# SCH_ymu762-1_2022-05-05.net
KiCad netlist of a schematic drawn in EasyEDA
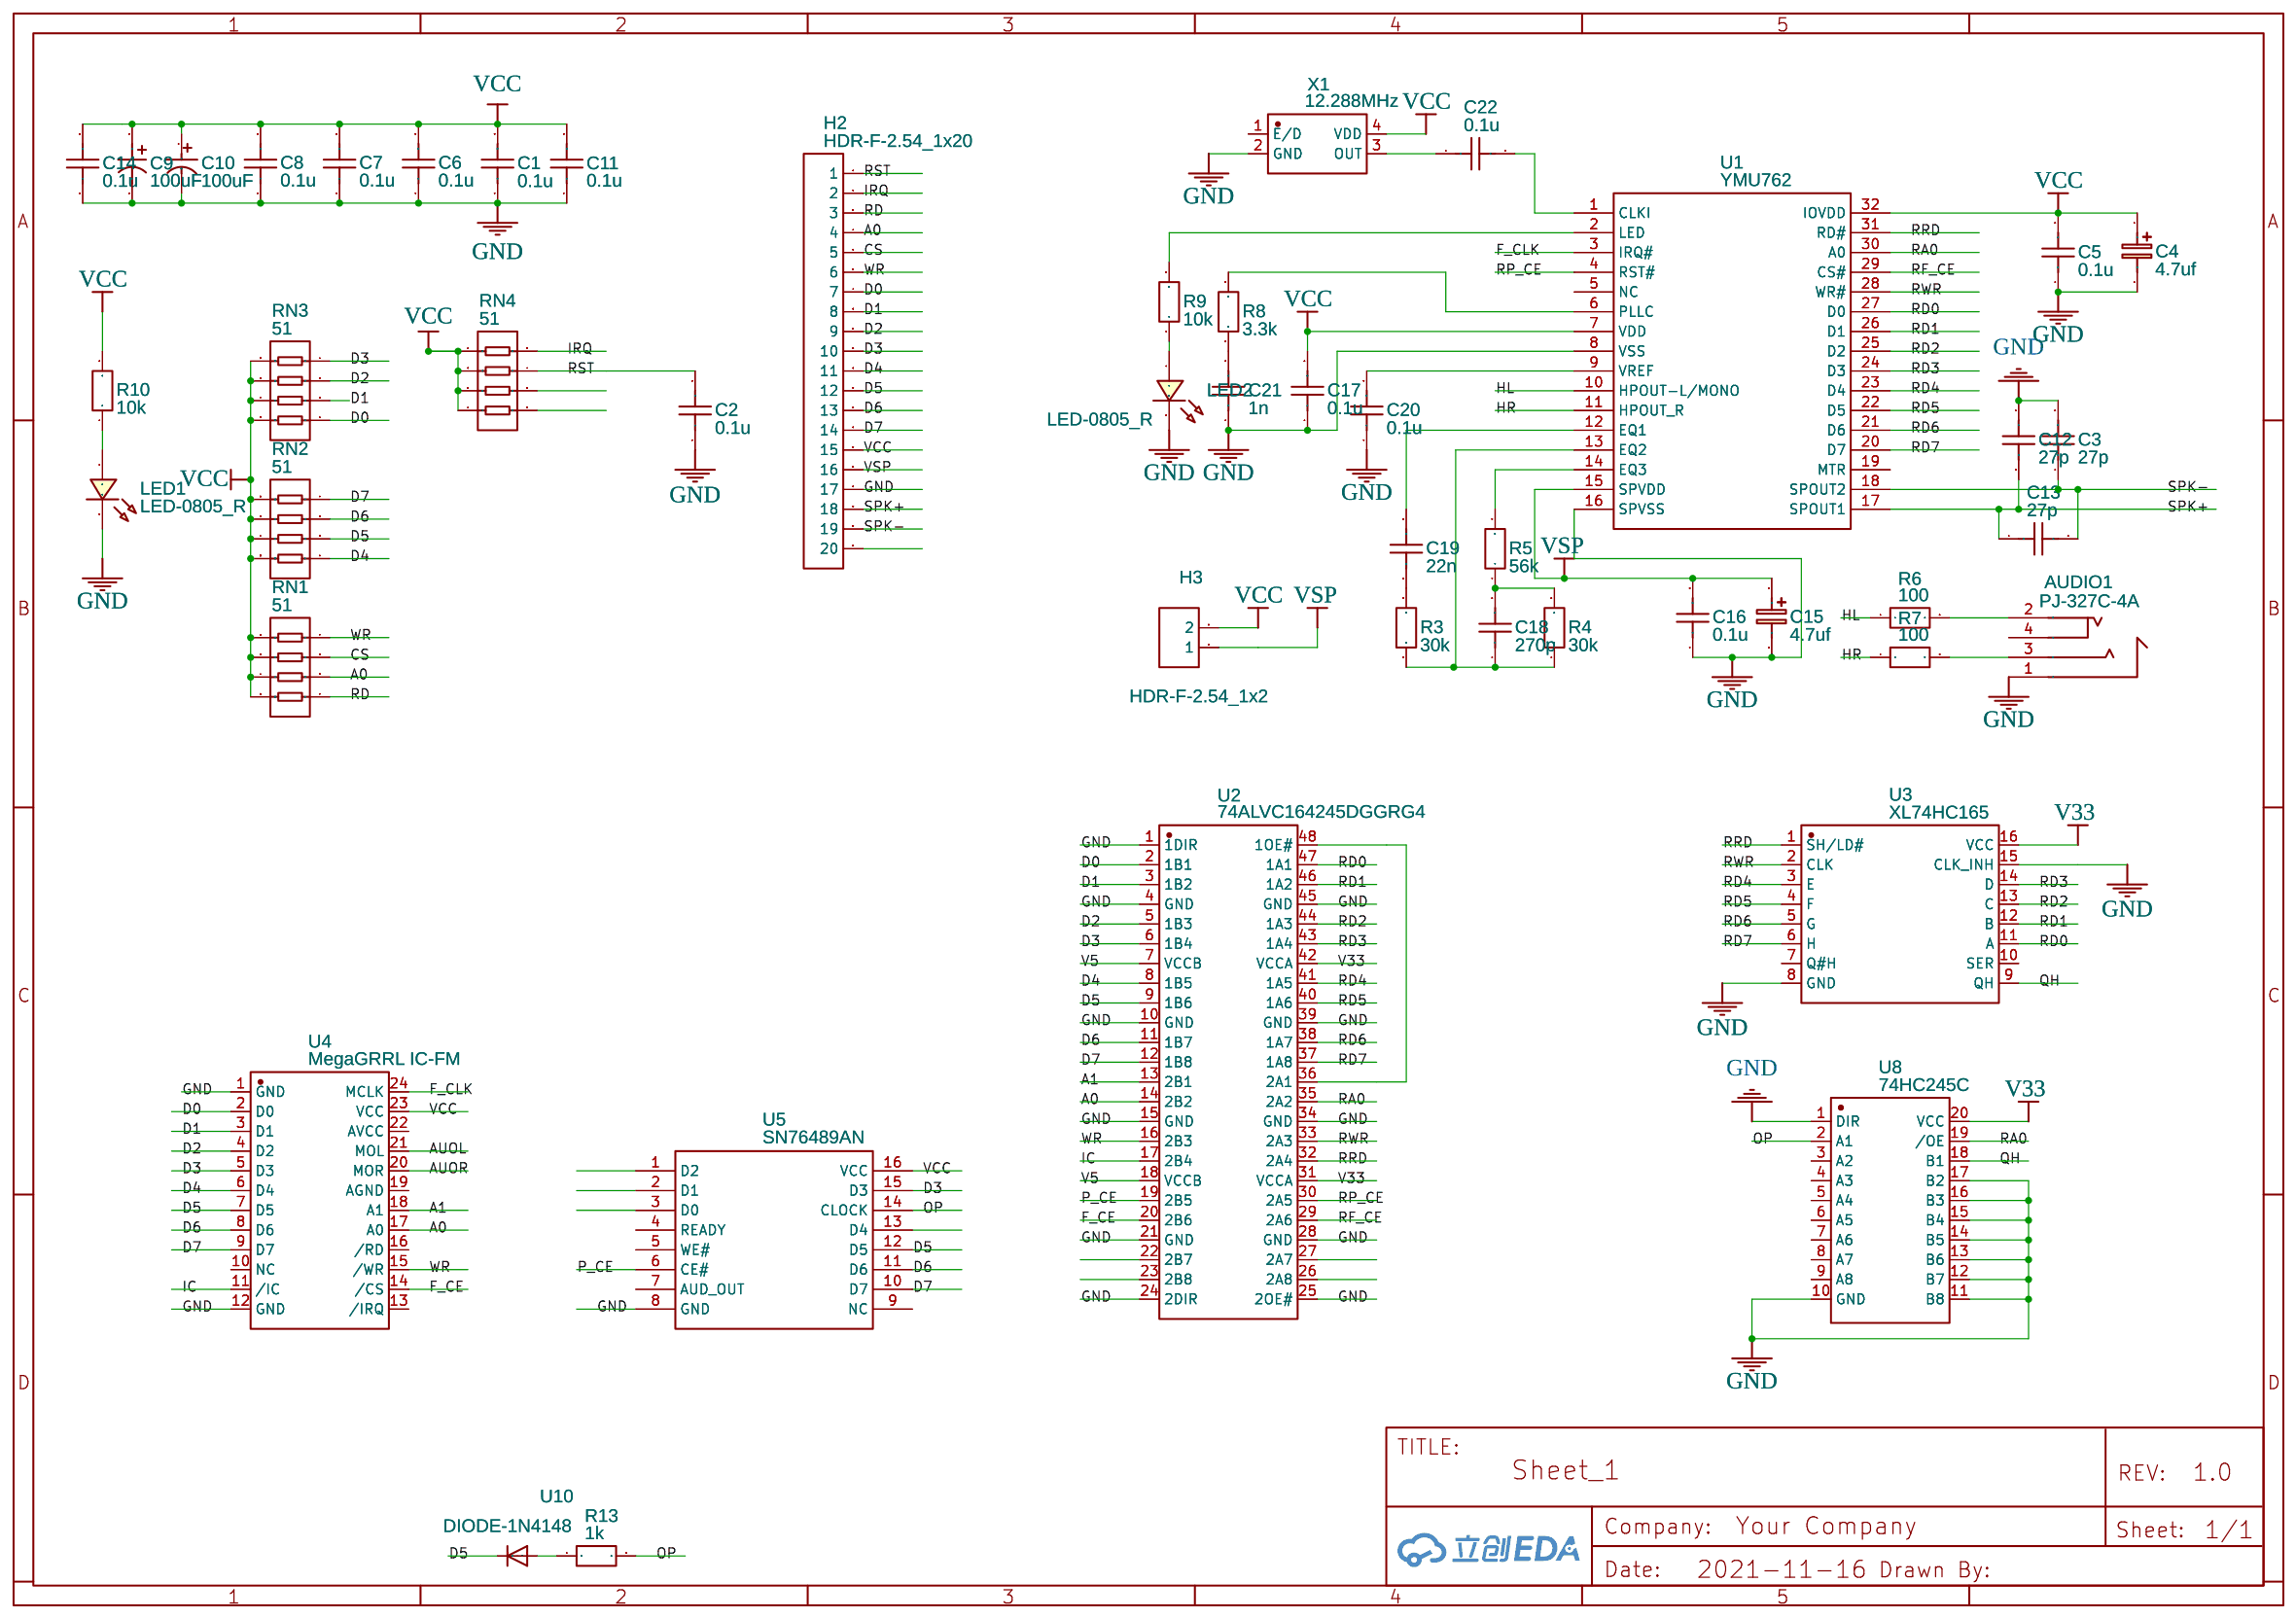
[diagram p0: schematic sheet]

(export (version "E")
  (design (tool "Eeschema 10.0.6"))
  (components
    (comp (ref "AUDIO1")
      (value "PJ-327C-4A")
      (fields (field (name "BOM_Supplier Part") "C145813"))
      (libsource (lib "") (part "PJ-327C-4A"))
    )
    (comp (ref "C1") (value "0.1u") (libsource (lib "") (part "C_0805_US")))
    (comp (ref "C2") (value "0.1u") (libsource (lib "") (part "C_0805_US")))
    (comp (ref "C3") (value "27p") (libsource (lib "") (part "C_0805_US")))
    (comp (ref "C4") (value "4.7uf") (libsource (lib "") (part "C_Tan_SMD_A_EU")))
    (comp (ref "C5") (value "0.1u") (libsource (lib "") (part "C_0805_US")))
    (comp (ref "C6") (value "0.1u") (libsource (lib "") (part "C_0805_US")))
    (comp (ref "C7") (value "0.1u") (libsource (lib "") (part "C_0805_US")))
    (comp (ref "C8") (value "0.1u") (libsource (lib "") (part "C_0805_US")))
    (comp (ref "C9")
      (value "100uF")
      (fields
        (field (name "BOM_Manufacturer Part") "RVT100UF35V67RV0034")
        (field (name "BOM_Supplier Part") "C2836442")
      )
      (libsource (lib "") (part "RVT100UF35V67RV0034"))
    )
    (comp (ref "C10")
      (value "100uF")
      (fields
        (field (name "BOM_Manufacturer Part") "63V 100uF 8X12")
        (field (name "BOM_Supplier Part") "C2772")
      )
      (libsource (lib "") (part "63V 100uF 8X12"))
    )
    (comp (ref "C11") (value "0.1u") (libsource (lib "") (part "C_0805_US")))
    (comp (ref "C12") (value "27p") (libsource (lib "") (part "C_0805_US_2")))
    (comp (ref "C13") (value "27p") (libsource (lib "") (part "C_0805_US_1")))
    (comp (ref "C14") (value "0.1u") (libsource (lib "") (part "C_0805_US")))
    (comp (ref "C15") (value "4.7uf") (libsource (lib "") (part "C_Tan_SMD_A_EU_1")))
    (comp (ref "C16") (value "0.1u") (libsource (lib "") (part "C_0805_US")))
    (comp (ref "C17") (value "0.1u") (libsource (lib "") (part "C_0805_US")))
    (comp (ref "C18") (value "270p") (libsource (lib "") (part "C_0805_US")))
    (comp (ref "C19") (value "22n") (libsource (lib "") (part "C_0805_US_2")))
    (comp (ref "C20") (value "0.1u") (libsource (lib "") (part "C_0805_US")))
    (comp (ref "C21") (value "1n") (libsource (lib "") (part "C_0805_US")))
    (comp (ref "C22") (value "0.1u") (libsource (lib "") (part "C_0805_US_1")))
    (comp (ref "H2")
      (value "HDR-F-2.54_1x20")
      (fields (field (name "BOM_Supplier Part") "C50984"))
      (libsource (lib "") (part "HDR-F-2.54_1x20"))
    )
    (comp (ref "H3")
      (value "HDR-F-2.54_1x2")
      (fields (field (name "BOM_Supplier Part") "C49661"))
      (libsource (lib "") (part "HDR-F-2.54_1x2"))
    )
    (comp (ref "LED1")
      (value "LED-0805_R")
      (fields
        (field (name "BOM_Manufacturer Part") "17-21SURC/S530-A3/TR8")
        (field (name "BOM_Supplier Part") "C72037")
      )
      (libsource (lib "") (part "LED-0805_R"))
    )
    (comp (ref "LED2")
      (value "LED-0805_R")
      (fields
        (field (name "BOM_Manufacturer Part") "17-21SURC/S530-A3/TR8")
        (field (name "BOM_Supplier Part") "C72037")
      )
      (libsource (lib "") (part "LED-0805_R"))
    )
    (comp (ref "R3") (value "30k") (libsource (lib "") (part "R_0805_EU")))
    (comp (ref "R4") (value "30k") (libsource (lib "") (part "R_0805_EU")))
    (comp (ref "R5") (value "56k") (libsource (lib "") (part "R_0805_EU")))
    (comp (ref "R6") (value "100") (libsource (lib "") (part "R_0805_EU_1")))
    (comp (ref "R7") (value "100") (libsource (lib "") (part "R_0805_EU_1")))
    (comp (ref "R8") (value "3.3k") (libsource (lib "") (part "R_0805_EU")))
    (comp (ref "R9") (value "10k") (libsource (lib "") (part "R_0805_EU")))
    (comp (ref "R10") (value "10k") (libsource (lib "") (part "R_0805_EU")))
    (comp (ref "R13") (value "1k") (libsource (lib "") (part "R_0805_EU_1")))
    (comp (ref "RN1")
      (value "51")
      (fields
        (field (name "BOM_Manufacturer Part") "YC164-JR-0751RL")
        (field (name "BOM_Supplier Part") "C13474")
      )
      (libsource (lib "") (part "YC164-JR-0751RL_1"))
    )
    (comp (ref "RN2")
      (value "51")
      (fields
        (field (name "BOM_Manufacturer Part") "YC164-JR-0751RL")
        (field (name "BOM_Supplier Part") "C13474")
      )
      (libsource (lib "") (part "YC164-JR-0751RL_1"))
    )
    (comp (ref "RN3")
      (value "51")
      (fields
        (field (name "BOM_Manufacturer Part") "YC164-JR-0751RL")
        (field (name "BOM_Supplier Part") "C13474")
      )
      (libsource (lib "") (part "YC164-JR-0751RL_1"))
    )
    (comp (ref "RN4")
      (value "51")
      (fields
        (field (name "BOM_Manufacturer Part") "YC164-JR-0751RL")
        (field (name "BOM_Supplier Part") "C13474")
      )
      (libsource (lib "") (part "YC164-JR-0751RL"))
    )
    (comp (ref "U1") (value "YMU762") (libsource (lib "") (part "YMU762")))
    (comp (ref "U2")
      (value "74ALVC164245DGGRG4")
      (fields (field (name "BOM_Supplier Part") "C2677427"))
      (libsource (lib "") (part "74ALVC164245DGGRG4"))
    )
    (comp (ref "U3")
      (value "XL74HC165")
      (fields (field (name "BOM_Supplier Part") "C609780"))
      (libsource (lib "") (part "XL74HC165"))
    )
    (comp (ref "U4")
      (value "MegaGRRL IC-FM")
      (fields (field (name "BOM_Manufacturer Part") "YM2612") (field (name "BOM_Supplier Part") "C707077"))
      (libsource (lib "") (part "MegaGRRL IC-FM"))
    )
    (comp (ref "U5") (value "SN76489AN") (libsource (lib "") (part "SN76489AN")))
    (comp (ref "U8")
      (value "74HC245C")
      (fields (field (name "BOM_Supplier Part") "C126198"))
      (libsource (lib "") (part "74HC245C"))
    )
    (comp (ref "U10") (value "DIODE-1N4148") (libsource (lib "") (part "DIODE-1N4148")))
    (comp (ref "X1")
      (value "12.288MHz")
      (fields
        (field (name "BOM_Manufacturer Part") "OT705012.288MJBA4SL")
        (field (name "BOM_Supplier Part") "C669092")
      )
      (libsource (lib "") (part "OT705012.288MJBA4SL"))
    )
  )
  (nets
    (net (code "1") (name "/A0") (class "Default")
      (node (ref "H2") (pin "4") (pinfunction "4_4") (pintype "unspecified"))
      (node (ref "RN1") (pin "2") (pinfunction "2_2") (pintype "unspecified"))
      (node (ref "U2") (pin "14") (pinfunction "2B2_14") (pintype "unspecified"))
      (node (ref "U4") (pin "17") (pinfunction "A0_17") (pintype "unspecified"))
    )
    (net (code "2") (name "/A1") (class "Default")
      (node (ref "U2") (pin "13") (pinfunction "2B1_13") (pintype "unspecified"))
      (node (ref "U4") (pin "18") (pinfunction "A1_18") (pintype "unspecified"))
    )
    (net (code "3") (name "/AUOL") (class "Default")
      (node (ref "U4") (pin "21") (pinfunction "MOL_21") (pintype "unspecified"))
    )
    (net (code "4") (name "/AUOR") (class "Default")
      (node (ref "U4") (pin "20") (pinfunction "MOR_20") (pintype "unspecified"))
    )
    (net (code "5") (name "/CS") (class "Default")
      (node (ref "H2") (pin "5") (pinfunction "5_5") (pintype "unspecified"))
      (node (ref "RN1") (pin "3") (pinfunction "3_3") (pintype "unspecified"))
    )
    (net (code "6") (name "/D0") (class "Default")
      (node (ref "H2") (pin "7") (pinfunction "7_7") (pintype "unspecified"))
      (node (ref "RN3") (pin "1") (pinfunction "1_1") (pintype "unspecified"))
      (node (ref "U2") (pin "2") (pinfunction "1B1_2") (pintype "unspecified"))
      (node (ref "U4") (pin "2") (pinfunction "D0_2") (pintype "unspecified"))
    )
    (net (code "7") (name "/D1") (class "Default")
      (node (ref "H2") (pin "8") (pinfunction "8_8") (pintype "unspecified"))
      (node (ref "RN3") (pin "2") (pinfunction "2_2") (pintype "unspecified"))
      (node (ref "U2") (pin "3") (pinfunction "1B2_3") (pintype "unspecified"))
      (node (ref "U4") (pin "3") (pinfunction "D1_3") (pintype "unspecified"))
    )
    (net (code "8") (name "/D2") (class "Default")
      (node (ref "H2") (pin "9") (pinfunction "9_9") (pintype "unspecified"))
      (node (ref "RN3") (pin "3") (pinfunction "3_3") (pintype "unspecified"))
      (node (ref "U2") (pin "5") (pinfunction "1B3_5") (pintype "unspecified"))
      (node (ref "U4") (pin "4") (pinfunction "D2_4") (pintype "unspecified"))
    )
    (net (code "9") (name "/D3") (class "Default")
      (node (ref "H2") (pin "10") (pinfunction "10_10") (pintype "unspecified"))
      (node (ref "RN3") (pin "4") (pinfunction "4_4") (pintype "unspecified"))
      (node (ref "U2") (pin "6") (pinfunction "1B4_6") (pintype "unspecified"))
      (node (ref "U4") (pin "5") (pinfunction "D3_5") (pintype "unspecified"))
      (node (ref "U5") (pin "15") (pinfunction "D3_15") (pintype "unspecified"))
    )
    (net (code "10") (name "/D4") (class "Default")
      (node (ref "H2") (pin "11") (pinfunction "11_11") (pintype "unspecified"))
      (node (ref "RN2") (pin "1") (pinfunction "1_1") (pintype "unspecified"))
      (node (ref "U2") (pin "8") (pinfunction "1B5_8") (pintype "unspecified"))
      (node (ref "U4") (pin "6") (pinfunction "D4_6") (pintype "unspecified"))
    )
    (net (code "11") (name "/D5") (class "Default")
      (node (ref "H2") (pin "12") (pinfunction "12_12") (pintype "unspecified"))
      (node (ref "RN2") (pin "2") (pinfunction "2_2") (pintype "unspecified"))
      (node (ref "U10") (pin "1") (pinfunction "C_1") (pintype "unspecified"))
      (node (ref "U2") (pin "9") (pinfunction "1B6_9") (pintype "unspecified"))
      (node (ref "U4") (pin "7") (pinfunction "D5_7") (pintype "unspecified"))
      (node (ref "U5") (pin "12") (pinfunction "D5_12") (pintype "unspecified"))
    )
    (net (code "12") (name "/D6") (class "Default")
      (node (ref "H2") (pin "13") (pinfunction "13_13") (pintype "unspecified"))
      (node (ref "RN2") (pin "3") (pinfunction "3_3") (pintype "unspecified"))
      (node (ref "U2") (pin "11") (pinfunction "1B7_11") (pintype "unspecified"))
      (node (ref "U4") (pin "8") (pinfunction "D6_8") (pintype "unspecified"))
      (node (ref "U5") (pin "11") (pinfunction "D6_11") (pintype "unspecified"))
    )
    (net (code "13") (name "/D7") (class "Default")
      (node (ref "H2") (pin "14") (pinfunction "14_14") (pintype "unspecified"))
      (node (ref "RN2") (pin "4") (pinfunction "4_4") (pintype "unspecified"))
      (node (ref "U2") (pin "12") (pinfunction "1B8_12") (pintype "unspecified"))
      (node (ref "U4") (pin "9") (pinfunction "D7_9") (pintype "unspecified"))
      (node (ref "U5") (pin "10") (pinfunction "D7_10") (pintype "unspecified"))
    )
    (net (code "14") (name "/F_CE") (class "Default")
      (node (ref "U2") (pin "20") (pinfunction "2B6_20") (pintype "unspecified"))
      (node (ref "U4") (pin "14") (pinfunction "/CS_14") (pintype "unspecified"))
    )
    (net (code "15") (name "/F_CLK") (class "Default")
      (node (ref "U1") (pin "3") (pinfunction "IRQ#_3") (pintype "unspecified"))
      (node (ref "U4") (pin "24") (pinfunction "MCLK_24") (pintype "unspecified"))
    )
    (net (code "16") (name "/HL") (class "Default")
      (node (ref "R6") (pin "1") (pinfunction "1_1") (pintype "unspecified"))
      (node (ref "U1") (pin "10") (pinfunction "HPOUT-L/MONO_10") (pintype "unspecified"))
    )
    (net (code "17") (name "/HR") (class "Default")
      (node (ref "R7") (pin "1") (pinfunction "1_1") (pintype "unspecified"))
      (node (ref "U1") (pin "11") (pinfunction "HPOUT_R_11") (pintype "unspecified"))
    )
    (net (code "18") (name "/IC") (class "Default")
      (node (ref "U2") (pin "17") (pinfunction "2B4_17") (pintype "unspecified"))
      (node (ref "U4") (pin "11") (pinfunction "/IC_11") (pintype "unspecified"))
    )
    (net (code "19") (name "/IRQ") (class "Default")
      (node (ref "H2") (pin "2") (pinfunction "2_2") (pintype "unspecified"))
      (node (ref "RN4") (pin "8") (pinfunction "8_8") (pintype "unspecified"))
    )
    (net (code "20") (name "/OP") (class "Default")
      (node (ref "R13") (pin "2") (pinfunction "2_2") (pintype "unspecified"))
      (node (ref "U5") (pin "14") (pinfunction "CLOCK_14") (pintype "unspecified"))
      (node (ref "U8") (pin "2") (pinfunction "A1_2") (pintype "unspecified"))
    )
    (net (code "21") (name "/P_CE") (class "Default")
      (node (ref "U2") (pin "19") (pinfunction "2B5_19") (pintype "unspecified"))
      (node (ref "U5") (pin "6") (pinfunction "CE#_6") (pintype "unspecified"))
    )
    (net (code "22") (name "/QH") (class "Default")
      (node (ref "U3") (pin "9") (pinfunction "QH_9") (pintype "unspecified"))
      (node (ref "U8") (pin "18") (pinfunction "B1_18") (pintype "unspecified"))
    )
    (net (code "23") (name "/RA0") (class "Default")
      (node (ref "U1") (pin "30") (pinfunction "A0_30") (pintype "unspecified"))
      (node (ref "U2") (pin "35") (pinfunction "2A2_35") (pintype "unspecified"))
      (node (ref "U8") (pin "19") (pinfunction "/OE_19") (pintype "unspecified"))
    )
    (net (code "24") (name "/RD") (class "Default")
      (node (ref "H2") (pin "3") (pinfunction "3_3") (pintype "unspecified"))
      (node (ref "RN1") (pin "1") (pinfunction "1_1") (pintype "unspecified"))
    )
    (net (code "25") (name "/RD0") (class "Default")
      (node (ref "U1") (pin "27") (pinfunction "D0_27") (pintype "unspecified"))
      (node (ref "U2") (pin "47") (pinfunction "1A1_47") (pintype "unspecified"))
      (node (ref "U3") (pin "11") (pinfunction "A_11") (pintype "unspecified"))
    )
    (net (code "26") (name "/RD1") (class "Default")
      (node (ref "U1") (pin "26") (pinfunction "D1_26") (pintype "unspecified"))
      (node (ref "U2") (pin "46") (pinfunction "1A2_46") (pintype "unspecified"))
      (node (ref "U3") (pin "12") (pinfunction "B_12") (pintype "unspecified"))
    )
    (net (code "27") (name "/RD2") (class "Default")
      (node (ref "U1") (pin "25") (pinfunction "D2_25") (pintype "unspecified"))
      (node (ref "U2") (pin "44") (pinfunction "1A3_44") (pintype "unspecified"))
      (node (ref "U3") (pin "13") (pinfunction "C_13") (pintype "unspecified"))
    )
    (net (code "28") (name "/RD3") (class "Default")
      (node (ref "U1") (pin "24") (pinfunction "D3_24") (pintype "unspecified"))
      (node (ref "U2") (pin "43") (pinfunction "1A4_43") (pintype "unspecified"))
      (node (ref "U3") (pin "14") (pinfunction "D_14") (pintype "unspecified"))
    )
    (net (code "29") (name "/RD4") (class "Default")
      (node (ref "U1") (pin "23") (pinfunction "D4_23") (pintype "unspecified"))
      (node (ref "U2") (pin "41") (pinfunction "1A5_41") (pintype "unspecified"))
      (node (ref "U3") (pin "3") (pinfunction "E_3") (pintype "unspecified"))
    )
    (net (code "30") (name "/RD5") (class "Default")
      (node (ref "U1") (pin "22") (pinfunction "D5_22") (pintype "unspecified"))
      (node (ref "U2") (pin "40") (pinfunction "1A6_40") (pintype "unspecified"))
      (node (ref "U3") (pin "4") (pinfunction "F_4") (pintype "unspecified"))
    )
    (net (code "31") (name "/RD6") (class "Default")
      (node (ref "U1") (pin "21") (pinfunction "D6_21") (pintype "unspecified"))
      (node (ref "U2") (pin "38") (pinfunction "1A7_38") (pintype "unspecified"))
      (node (ref "U3") (pin "5") (pinfunction "G_5") (pintype "unspecified"))
    )
    (net (code "32") (name "/RD7") (class "Default")
      (node (ref "U1") (pin "20") (pinfunction "D7_20") (pintype "unspecified"))
      (node (ref "U2") (pin "37") (pinfunction "1A8_37") (pintype "unspecified"))
      (node (ref "U3") (pin "6") (pinfunction "H_6") (pintype "unspecified"))
    )
    (net (code "33") (name "/RF_CE") (class "Default")
      (node (ref "U1") (pin "29") (pinfunction "CS#_29") (pintype "unspecified"))
      (node (ref "U2") (pin "29") (pinfunction "2A6_29") (pintype "unspecified"))
    )
    (net (code "34") (name "/RP_CE") (class "Default")
      (node (ref "U1") (pin "4") (pinfunction "RST#_4") (pintype "unspecified"))
      (node (ref "U2") (pin "30") (pinfunction "2A5_30") (pintype "unspecified"))
    )
    (net (code "35") (name "/RRD") (class "Default")
      (node (ref "U1") (pin "31") (pinfunction "RD#_31") (pintype "unspecified"))
      (node (ref "U2") (pin "32") (pinfunction "2A4_32") (pintype "unspecified"))
      (node (ref "U3") (pin "1") (pinfunction "SH/LD#_1") (pintype "unspecified"))
    )
    (net (code "36") (name "/RST") (class "Default")
      (node (ref "C2") (pin "2") (pinfunction "2_2") (pintype "unspecified"))
      (node (ref "H2") (pin "1") (pinfunction "1_1") (pintype "unspecified"))
      (node (ref "RN4") (pin "7") (pinfunction "7_7") (pintype "unspecified"))
    )
    (net (code "37") (name "/RWR") (class "Default")
      (node (ref "U1") (pin "28") (pinfunction "WR#_28") (pintype "unspecified"))
      (node (ref "U2") (pin "33") (pinfunction "2A3_33") (pintype "unspecified"))
      (node (ref "U3") (pin "2") (pinfunction "CLK_2") (pintype "unspecified"))
    )
    (net (code "38") (name "/SPK+") (class "Default")
      (node (ref "C12") (pin "2") (pinfunction "2_2") (pintype "unspecified"))
      (node (ref "C13") (pin "1") (pinfunction "1_1") (pintype "unspecified"))
      (node (ref "H2") (pin "18") (pinfunction "18_18") (pintype "unspecified"))
      (node (ref "U1") (pin "17") (pinfunction "SPOUT1_17") (pintype "unspecified"))
    )
    (net (code "39") (name "/SPK-") (class "Default")
      (node (ref "C13") (pin "2") (pinfunction "2_2") (pintype "unspecified"))
      (node (ref "C3") (pin "1") (pinfunction "1_1") (pintype "unspecified"))
      (node (ref "H2") (pin "19") (pinfunction "19_19") (pintype "unspecified"))
      (node (ref "U1") (pin "18") (pinfunction "SPOUT2_18") (pintype "unspecified"))
    )
    (net (code "40") (name "/V5") (class "Default")
      (node (ref "U2") (pin "18") (pinfunction "VCCB_18") (pintype "unspecified"))
      (node (ref "U2") (pin "7") (pinfunction "VCCB_7") (pintype "unspecified"))
    )
    (net (code "41") (name "/WR") (class "Default")
      (node (ref "H2") (pin "6") (pinfunction "6_6") (pintype "unspecified"))
      (node (ref "RN1") (pin "4") (pinfunction "4_4") (pintype "unspecified"))
      (node (ref "U2") (pin "16") (pinfunction "2B3_16") (pintype "unspecified"))
      (node (ref "U4") (pin "15") (pinfunction "/WR_15") (pintype "unspecified"))
    )
    (net (code "42") (name "GND") (class "Default")
      (node (ref "AUDIO1") (pin "1") (pinfunction "1_1") (pintype "unspecified"))
      (node (ref "C1") (pin "1") (pinfunction "1_1") (pintype "unspecified"))
      (node (ref "C10") (pin "2") (pinfunction "2_2") (pintype "input"))
      (node (ref "C11") (pin "1") (pinfunction "1_1") (pintype "unspecified"))
      (node (ref "C12") (pin "1") (pinfunction "1_1") (pintype "unspecified"))
      (node (ref "C14") (pin "1") (pinfunction "1_1") (pintype "unspecified"))
      (node (ref "C15") (pin "2") (pinfunction "2_2") (pintype "unspecified"))
      (node (ref "C16") (pin "1") (pinfunction "1_1") (pintype "unspecified"))
      (node (ref "C17") (pin "1") (pinfunction "1_1") (pintype "unspecified"))
      (node (ref "C2") (pin "1") (pinfunction "1_1") (pintype "unspecified"))
      (node (ref "C20") (pin "1") (pinfunction "1_1") (pintype "unspecified"))
      (node (ref "C21") (pin "1") (pinfunction "1_1") (pintype "unspecified"))
      (node (ref "C3") (pin "2") (pinfunction "2_2") (pintype "unspecified"))
      (node (ref "C4") (pin "2") (pinfunction "2_2") (pintype "unspecified"))
      (node (ref "C5") (pin "1") (pinfunction "1_1") (pintype "unspecified"))
      (node (ref "C6") (pin "1") (pinfunction "1_1") (pintype "unspecified"))
      (node (ref "C7") (pin "1") (pinfunction "1_1") (pintype "unspecified"))
      (node (ref "C8") (pin "1") (pinfunction "1_1") (pintype "unspecified"))
      (node (ref "C9") (pin "2") (pinfunction "2_2") (pintype "input"))
      (node (ref "H2") (pin "17") (pinfunction "17_17") (pintype "unspecified"))
      (node (ref "LED1") (pin "2") (pinfunction "2_2") (pintype "unspecified"))
      (node (ref "LED2") (pin "2") (pinfunction "2_2") (pintype "unspecified"))
      (node (ref "U1") (pin "16") (pinfunction "SPVSS_16") (pintype "unspecified"))
      (node (ref "U1") (pin "8") (pinfunction "VSS_8") (pintype "unspecified"))
      (node (ref "U2") (pin "1") (pinfunction "1DIR_1") (pintype "unspecified"))
      (node (ref "U2") (pin "10") (pinfunction "GND_10") (pintype "unspecified"))
      (node (ref "U2") (pin "15") (pinfunction "GND_15") (pintype "unspecified"))
      (node (ref "U2") (pin "21") (pinfunction "GND_21") (pintype "unspecified"))
      (node (ref "U2") (pin "24") (pinfunction "2DIR_24") (pintype "unspecified"))
      (node (ref "U2") (pin "25") (pinfunction "2OE#_25") (pintype "unspecified"))
      (node (ref "U2") (pin "28") (pinfunction "GND_28") (pintype "unspecified"))
      (node (ref "U2") (pin "34") (pinfunction "GND_34") (pintype "unspecified"))
      (node (ref "U2") (pin "39") (pinfunction "GND_39") (pintype "unspecified"))
      (node (ref "U2") (pin "4") (pinfunction "GND_4") (pintype "unspecified"))
      (node (ref "U2") (pin "45") (pinfunction "GND_45") (pintype "unspecified"))
      (node (ref "U3") (pin "15") (pinfunction "CLK_INH_15") (pintype "unspecified"))
      (node (ref "U3") (pin "8") (pinfunction "GND_8") (pintype "unspecified"))
      (node (ref "U4") (pin "1") (pinfunction "GND_1") (pintype "unspecified"))
      (node (ref "U4") (pin "12") (pinfunction "GND_12") (pintype "unspecified"))
      (node (ref "U5") (pin "8") (pinfunction "GND_8") (pintype "unspecified"))
      (node (ref "U8") (pin "1") (pinfunction "DIR_1") (pintype "unspecified"))
      (node (ref "U8") (pin "10") (pinfunction "GND_10") (pintype "unspecified"))
      (node (ref "U8") (pin "11") (pinfunction "B8_11") (pintype "unspecified"))
      (node (ref "U8") (pin "12") (pinfunction "B7_12") (pintype "unspecified"))
      (node (ref "U8") (pin "13") (pinfunction "B6_13") (pintype "unspecified"))
      (node (ref "U8") (pin "14") (pinfunction "B5_14") (pintype "unspecified"))
      (node (ref "U8") (pin "15") (pinfunction "B4_15") (pintype "unspecified"))
      (node (ref "U8") (pin "16") (pinfunction "B3_16") (pintype "unspecified"))
      (node (ref "U8") (pin "17") (pinfunction "B2_17") (pintype "unspecified"))
      (node (ref "X1") (pin "2") (pinfunction "GND_2") (pintype "unspecified"))
    )
    (net (code "43") (name "Net-(AUDIO1-Pad2)") (class "Default")
      (node (ref "AUDIO1") (pin "2") (pinfunction "2_2") (pintype "unspecified"))
      (node (ref "R6") (pin "2") (pinfunction "2_2") (pintype "unspecified"))
    )
    (net (code "44") (name "Net-(AUDIO1-Pad3)") (class "Default")
      (node (ref "AUDIO1") (pin "3") (pinfunction "3_3") (pintype "unspecified"))
      (node (ref "R7") (pin "2") (pinfunction "2_2") (pintype "unspecified"))
    )
    (net (code "45") (name "Net-(C18-Pad2)") (class "Default")
      (node (ref "C18") (pin "2") (pinfunction "2_2") (pintype "unspecified"))
      (node (ref "R4") (pin "2") (pinfunction "2_2") (pintype "unspecified"))
      (node (ref "R5") (pin "1") (pinfunction "1_1") (pintype "unspecified"))
    )
    (net (code "46") (name "Net-(C19-Pad2)") (class "Default")
      (node (ref "C19") (pin "2") (pinfunction "2_2") (pintype "unspecified"))
      (node (ref "R3") (pin "2") (pinfunction "2_2") (pintype "unspecified"))
    )
    (net (code "47") (name "Net-(C21-Pad2)") (class "Default")
      (node (ref "C21") (pin "2") (pinfunction "2_2") (pintype "unspecified"))
      (node (ref "R8") (pin "1") (pinfunction "1_1") (pintype "unspecified"))
    )
    (net (code "48") (name "Net-(LED1-Pad1)") (class "Default")
      (node (ref "LED1") (pin "1") (pinfunction "1_1") (pintype "unspecified"))
      (node (ref "R10") (pin "1") (pinfunction "1_1") (pintype "unspecified"))
    )
    (net (code "49") (name "Net-(LED2-Pad1)") (class "Default")
      (node (ref "LED2") (pin "1") (pinfunction "1_1") (pintype "unspecified"))
      (node (ref "R9") (pin "1") (pinfunction "1_1") (pintype "unspecified"))
    )
    (net (code "50") (name "Net-(U1-CLKI)") (class "Default")
      (node (ref "C22") (pin "2") (pinfunction "2_2") (pintype "unspecified"))
      (node (ref "U1") (pin "1") (pinfunction "CLKI_1") (pintype "unspecified"))
    )
    (net (code "51") (name "Net-(U1-EQ1)") (class "Default")
      (node (ref "C19") (pin "1") (pinfunction "1_1") (pintype "unspecified"))
      (node (ref "U1") (pin "12") (pinfunction "EQ1_12") (pintype "unspecified"))
    )
    (net (code "52") (name "Net-(U1-EQ2)") (class "Default")
      (node (ref "C18") (pin "1") (pinfunction "1_1") (pintype "unspecified"))
      (node (ref "R3") (pin "1") (pinfunction "1_1") (pintype "unspecified"))
      (node (ref "R4") (pin "1") (pinfunction "1_1") (pintype "unspecified"))
      (node (ref "U1") (pin "13") (pinfunction "EQ2_13") (pintype "unspecified"))
    )
    (net (code "53") (name "Net-(U1-EQ3)") (class "Default")
      (node (ref "R5") (pin "2") (pinfunction "2_2") (pintype "unspecified"))
      (node (ref "U1") (pin "14") (pinfunction "EQ3_14") (pintype "unspecified"))
    )
    (net (code "54") (name "Net-(U1-LED)") (class "Default")
      (node (ref "R9") (pin "2") (pinfunction "2_2") (pintype "unspecified"))
      (node (ref "U1") (pin "2") (pinfunction "LED_2") (pintype "unspecified"))
    )
    (net (code "55") (name "Net-(U1-PLLC)") (class "Default")
      (node (ref "R8") (pin "2") (pinfunction "2_2") (pintype "unspecified"))
      (node (ref "U1") (pin "6") (pinfunction "PLLC_6") (pintype "unspecified"))
    )
    (net (code "56") (name "Net-(U1-VREF)") (class "Default")
      (node (ref "C20") (pin "2") (pinfunction "2_2") (pintype "unspecified"))
      (node (ref "U1") (pin "9") (pinfunction "VREF_9") (pintype "unspecified"))
    )
    (net (code "57") (name "Net-(U2-1OE#)") (class "Default")
      (node (ref "U2") (pin "36") (pinfunction "2A1_36") (pintype "unspecified"))
      (node (ref "U2") (pin "48") (pinfunction "1OE#_48") (pintype "unspecified"))
    )
    (net (code "58") (name "Net-(U10-A)") (class "Default")
      (node (ref "R13") (pin "1") (pinfunction "1_1") (pintype "unspecified"))
      (node (ref "U10") (pin "2") (pinfunction "A_2") (pintype "unspecified"))
    )
    (net (code "59") (name "Net-(X1-OUT)") (class "Default")
      (node (ref "C22") (pin "1") (pinfunction "1_1") (pintype "unspecified"))
      (node (ref "X1") (pin "3") (pinfunction "OUT_3") (pintype "unspecified"))
    )
    (net (code "60") (name "V33") (class "Default")
      (node (ref "U2") (pin "31") (pinfunction "VCCA_31") (pintype "unspecified"))
      (node (ref "U2") (pin "42") (pinfunction "VCCA_42") (pintype "unspecified"))
      (node (ref "U3") (pin "16") (pinfunction "VCC_16") (pintype "unspecified"))
      (node (ref "U8") (pin "20") (pinfunction "VCC_20") (pintype "unspecified"))
    )
    (net (code "61") (name "VCC") (class "Default")
      (node (ref "C1") (pin "2") (pinfunction "2_2") (pintype "unspecified"))
      (node (ref "C10") (pin "1") (pinfunction "1_1") (pintype "input"))
      (node (ref "C11") (pin "2") (pinfunction "2_2") (pintype "unspecified"))
      (node (ref "C14") (pin "2") (pinfunction "2_2") (pintype "unspecified"))
      (node (ref "C17") (pin "2") (pinfunction "2_2") (pintype "unspecified"))
      (node (ref "C4") (pin "1") (pinfunction "1_1") (pintype "unspecified"))
      (node (ref "C5") (pin "2") (pinfunction "2_2") (pintype "unspecified"))
      (node (ref "C6") (pin "2") (pinfunction "2_2") (pintype "unspecified"))
      (node (ref "C7") (pin "2") (pinfunction "2_2") (pintype "unspecified"))
      (node (ref "C8") (pin "2") (pinfunction "2_2") (pintype "unspecified"))
      (node (ref "C9") (pin "1") (pinfunction "1_1") (pintype "input"))
      (node (ref "H2") (pin "15") (pinfunction "15_15") (pintype "unspecified"))
      (node (ref "H3") (pin "2") (pinfunction "2_2") (pintype "input"))
      (node (ref "R10") (pin "2") (pinfunction "2_2") (pintype "unspecified"))
      (node (ref "RN1") (pin "5") (pinfunction "5_5") (pintype "unspecified"))
      (node (ref "RN1") (pin "6") (pinfunction "6_6") (pintype "unspecified"))
      (node (ref "RN1") (pin "7") (pinfunction "7_7") (pintype "unspecified"))
      (node (ref "RN1") (pin "8") (pinfunction "8_8") (pintype "unspecified"))
      (node (ref "RN2") (pin "5") (pinfunction "5_5") (pintype "unspecified"))
      (node (ref "RN2") (pin "6") (pinfunction "6_6") (pintype "unspecified"))
      (node (ref "RN2") (pin "7") (pinfunction "7_7") (pintype "unspecified"))
      (node (ref "RN2") (pin "8") (pinfunction "8_8") (pintype "unspecified"))
      (node (ref "RN3") (pin "5") (pinfunction "5_5") (pintype "unspecified"))
      (node (ref "RN3") (pin "6") (pinfunction "6_6") (pintype "unspecified"))
      (node (ref "RN3") (pin "7") (pinfunction "7_7") (pintype "unspecified"))
      (node (ref "RN3") (pin "8") (pinfunction "8_8") (pintype "unspecified"))
      (node (ref "RN4") (pin "1") (pinfunction "1_1") (pintype "unspecified"))
      (node (ref "RN4") (pin "2") (pinfunction "2_2") (pintype "unspecified"))
      (node (ref "RN4") (pin "3") (pinfunction "3_3") (pintype "unspecified"))
      (node (ref "RN4") (pin "4") (pinfunction "4_4") (pintype "unspecified"))
      (node (ref "U1") (pin "32") (pinfunction "IOVDD_32") (pintype "unspecified"))
      (node (ref "U1") (pin "7") (pinfunction "VDD_7") (pintype "unspecified"))
      (node (ref "U4") (pin "23") (pinfunction "VCC_23") (pintype "unspecified"))
      (node (ref "U5") (pin "16") (pinfunction "VCC_16") (pintype "unspecified"))
      (node (ref "X1") (pin "4") (pinfunction "VDD_4") (pintype "unspecified"))
    )
    (net (code "62") (name "VSP") (class "Default")
      (node (ref "C15") (pin "1") (pinfunction "1_1") (pintype "unspecified"))
      (node (ref "C16") (pin "2") (pinfunction "2_2") (pintype "unspecified"))
      (node (ref "H2") (pin "16") (pinfunction "16_16") (pintype "unspecified"))
      (node (ref "H3") (pin "1") (pinfunction "1_1") (pintype "input"))
      (node (ref "U1") (pin "15") (pinfunction "SPVDD_15") (pintype "unspecified"))
    )
    (net (code "63") (name "unconnected-(AUDIO1-Pad4)") (class "Default")
      (node (ref "AUDIO1") (pin "4") (pinfunction "4_4") (pintype "unspecified"))
    )
    (net (code "64") (name "unconnected-(H2-Pad20)") (class "Default")
      (node (ref "H2") (pin "20") (pinfunction "20_20") (pintype "unspecified"))
    )
    (net (code "65") (name "unconnected-(RN4-Pad5)") (class "Default")
      (node (ref "RN4") (pin "5") (pinfunction "5_5") (pintype "unspecified"))
    )
    (net (code "66") (name "unconnected-(RN4-Pad6)") (class "Default")
      (node (ref "RN4") (pin "6") (pinfunction "6_6") (pintype "unspecified"))
    )
    (net (code "67") (name "unconnected-(U1-MTR-Pad19)") (class "Default")
      (node (ref "U1") (pin "19") (pinfunction "MTR_19") (pintype "unspecified"))
    )
    (net (code "68") (name "unconnected-(U1-NC-Pad5)") (class "Default")
      (node (ref "U1") (pin "5") (pinfunction "NC_5") (pintype "unspecified"))
    )
    (net (code "69") (name "unconnected-(U2-2A7-Pad27)") (class "Default")
      (node (ref "U2") (pin "27") (pinfunction "2A7_27") (pintype "unspecified"))
    )
    (net (code "70") (name "unconnected-(U2-2A8-Pad26)") (class "Default")
      (node (ref "U2") (pin "26") (pinfunction "2A8_26") (pintype "unspecified"))
    )
    (net (code "71") (name "unconnected-(U2-2B7-Pad22)") (class "Default")
      (node (ref "U2") (pin "22") (pinfunction "2B7_22") (pintype "unspecified"))
    )
    (net (code "72") (name "unconnected-(U2-2B8-Pad23)") (class "Default")
      (node (ref "U2") (pin "23") (pinfunction "2B8_23") (pintype "unspecified"))
    )
    (net (code "73") (name "unconnected-(U3-Q#H-Pad7)") (class "Default")
      (node (ref "U3") (pin "7") (pinfunction "Q#H_7") (pintype "unspecified"))
    )
    (net (code "74") (name "unconnected-(U3-SER-Pad10)") (class "Default")
      (node (ref "U3") (pin "10") (pinfunction "SER_10") (pintype "unspecified"))
    )
    (net (code "75") (name "unconnected-(U4-AGND-Pad19)") (class "Default")
      (node (ref "U4") (pin "19") (pinfunction "AGND_19") (pintype "unspecified"))
    )
    (net (code "76") (name "unconnected-(U4-AVCC-Pad22)") (class "Default")
      (node (ref "U4") (pin "22") (pinfunction "AVCC_22") (pintype "unspecified"))
    )
    (net (code "77") (name "unconnected-(U4-NC-Pad10)") (class "Default")
      (node (ref "U4") (pin "10") (pinfunction "NC_10") (pintype "unspecified"))
    )
    (net (code "78") (name "unconnected-(U4-{slash}IRQ-Pad13)") (class "Default")
      (node (ref "U4") (pin "13") (pinfunction "/IRQ_13") (pintype "unspecified"))
    )
    (net (code "79") (name "unconnected-(U4-{slash}RD-Pad16)") (class "Default")
      (node (ref "U4") (pin "16") (pinfunction "/RD_16") (pintype "unspecified"))
    )
    (net (code "80") (name "unconnected-(U5-AUD_OUT-Pad7)") (class "Default")
      (node (ref "U5") (pin "7") (pinfunction "AUD_OUT_7") (pintype "unspecified"))
    )
    (net (code "81") (name "unconnected-(U5-D0-Pad3)") (class "Default")
      (node (ref "U5") (pin "3") (pinfunction "D0_3") (pintype "unspecified"))
    )
    (net (code "82") (name "unconnected-(U5-D1-Pad2)") (class "Default")
      (node (ref "U5") (pin "2") (pinfunction "D1_2") (pintype "unspecified"))
    )
    (net (code "83") (name "unconnected-(U5-D2-Pad1)") (class "Default")
      (node (ref "U5") (pin "1") (pinfunction "D2_1") (pintype "unspecified"))
    )
    (net (code "84") (name "unconnected-(U5-D4-Pad13)") (class "Default")
      (node (ref "U5") (pin "13") (pinfunction "D4_13") (pintype "unspecified"))
    )
    (net (code "85") (name "unconnected-(U5-NC-Pad9)") (class "Default")
      (node (ref "U5") (pin "9") (pinfunction "NC_9") (pintype "unspecified"))
    )
    (net (code "86") (name "unconnected-(U5-READY-Pad4)") (class "Default")
      (node (ref "U5") (pin "4") (pinfunction "READY_4") (pintype "unspecified"))
    )
    (net (code "87") (name "unconnected-(U5-WE#-Pad5)") (class "Default")
      (node (ref "U5") (pin "5") (pinfunction "WE#_5") (pintype "unspecified"))
    )
    (net (code "88") (name "unconnected-(U8-A2-Pad3)") (class "Default")
      (node (ref "U8") (pin "3") (pinfunction "A2_3") (pintype "unspecified"))
    )
    (net (code "89") (name "unconnected-(U8-A3-Pad4)") (class "Default")
      (node (ref "U8") (pin "4") (pinfunction "A3_4") (pintype "unspecified"))
    )
    (net (code "90") (name "unconnected-(U8-A4-Pad5)") (class "Default")
      (node (ref "U8") (pin "5") (pinfunction "A4_5") (pintype "unspecified"))
    )
    (net (code "91") (name "unconnected-(U8-A5-Pad6)") (class "Default")
      (node (ref "U8") (pin "6") (pinfunction "A5_6") (pintype "unspecified"))
    )
    (net (code "92") (name "unconnected-(U8-A6-Pad7)") (class "Default")
      (node (ref "U8") (pin "7") (pinfunction "A6_7") (pintype "unspecified"))
    )
    (net (code "93") (name "unconnected-(U8-A7-Pad8)") (class "Default")
      (node (ref "U8") (pin "8") (pinfunction "A7_8") (pintype "unspecified"))
    )
    (net (code "94") (name "unconnected-(U8-A8-Pad9)") (class "Default")
      (node (ref "U8") (pin "9") (pinfunction "A8_9") (pintype "unspecified"))
    )
    (net (code "95") (name "unconnected-(X1-E{slash}D-Pad1)") (class "Default")
      (node (ref "X1") (pin "1") (pinfunction "E/D_1") (pintype "unspecified"))
    )
  )
)
